# tinyGIANT.net
KiCad netlist of a schematic drawn in EAGLE
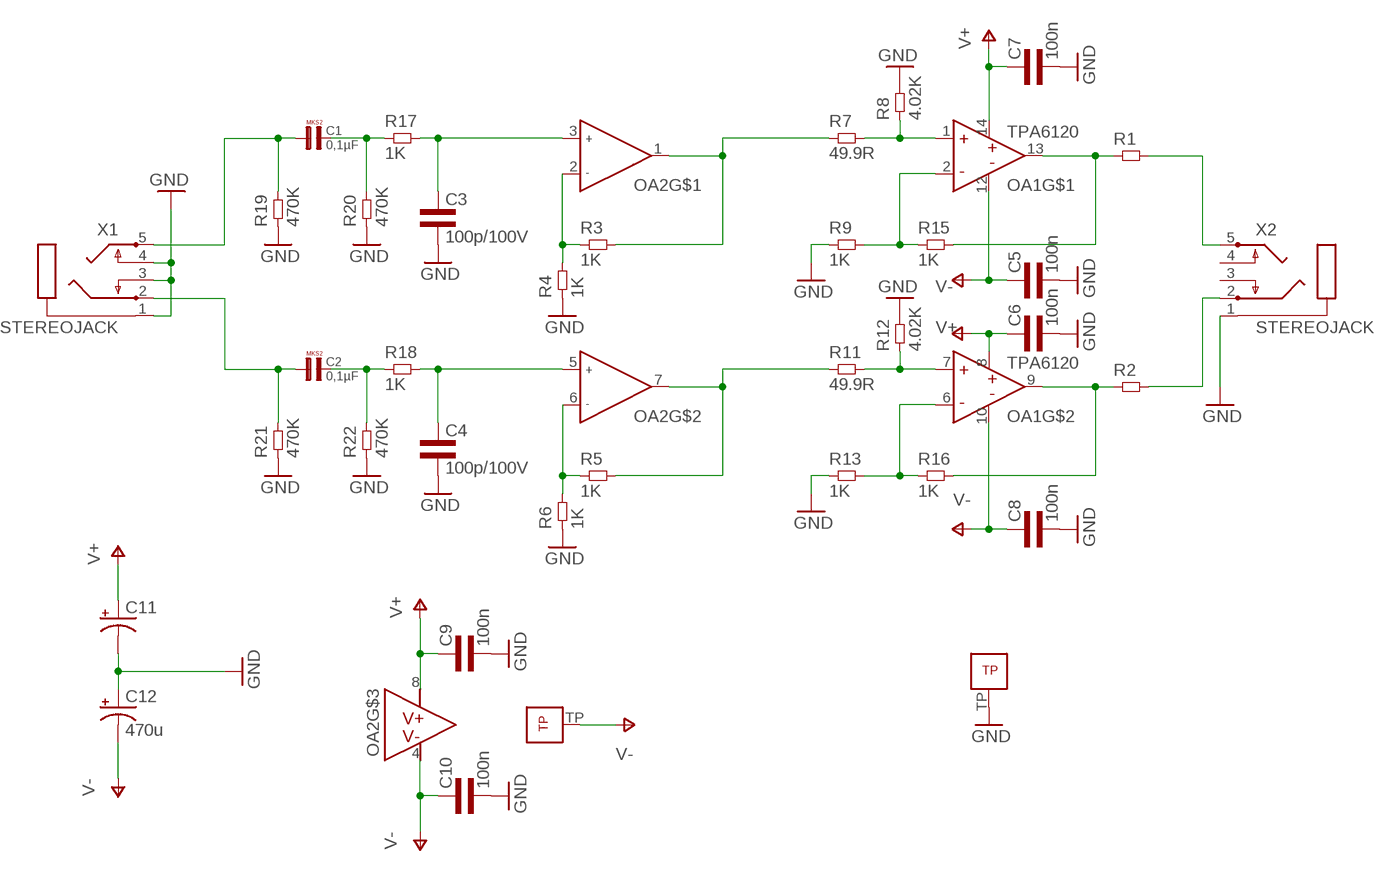
[diagram p0: schematic, sheet 1]

(export (version "E")
  (design (tool "Eeschema 10.0.6"))
  (components
    (comp (ref "C1")
      (value "0,1µF")
      (footprint "eagle-import:R5B2K5")
      (libsource (lib "eagle-import") (part "0,1µF"))
    )
    (comp (ref "C2")
      (value "0,1µF")
      (footprint "eagle-import:R5B2K5")
      (libsource (lib "eagle-import") (part "0,1µF"))
    )
    (comp (ref "C3")
      (value "100p/100V")
      (footprint "eagle-import:0805L3")
      (libsource (lib "eagle-import") (part "CAP0805L3"))
    )
    (comp (ref "C4")
      (value "100p/100V")
      (footprint "eagle-import:0805L3")
      (libsource (lib "eagle-import") (part "CAP0805L3"))
    )
    (comp (ref "C5")
      (value "100n")
      (footprint "eagle-import:0603L3")
      (libsource (lib "eagle-import") (part "CAP0603L3"))
    )
    (comp (ref "C6")
      (value "100n")
      (footprint "eagle-import:0603L3")
      (libsource (lib "eagle-import") (part "CAP0603L3"))
    )
    (comp (ref "C7")
      (value "100n")
      (footprint "eagle-import:0603L3")
      (libsource (lib "eagle-import") (part "CAP0603L3"))
    )
    (comp (ref "C8")
      (value "100n")
      (footprint "eagle-import:0603L3")
      (libsource (lib "eagle-import") (part "CAP0603L3"))
    )
    (comp (ref "C9")
      (value "100n")
      (footprint "eagle-import:0603L3")
      (libsource (lib "eagle-import") (part "CAP0603L3"))
    )
    (comp (ref "C10")
      (value "100n")
      (footprint "eagle-import:0603L3")
      (libsource (lib "eagle-import") (part "CAP0603L3"))
    )
    (comp (ref "C11")
      (value "CPOL-USCT7343")
      (footprint "eagle-import:CT7343")
      (libsource (lib "eagle-import") (part "CPOL-USCT7343"))
    )
    (comp (ref "C12")
      (value "470u")
      (footprint "eagle-import:CT7343")
      (libsource (lib "eagle-import") (part "CPOL-USCT7343"))
    )
    (comp (ref "OA1")
      (value "TPA6120QFN")
      (footprint "eagle-import:S-PVQFN-N14")
      (libsource (lib "eagle-import") (part "TPA6120QFN"))
    )
    (comp (ref "OA2")
      (value "OPA1612")
      (footprint "eagle-import:S-PWSON-N8")
      (libsource (lib "eagle-import") (part "OPA1612"))
    )
    (comp (ref "R1")
      (value "RES1206L3")
      (footprint "eagle-import:1206L3")
      (libsource (lib "eagle-import") (part "RES1206L3"))
    )
    (comp (ref "R2")
      (value "RES1206L3")
      (footprint "eagle-import:1206L3")
      (libsource (lib "eagle-import") (part "RES1206L3"))
    )
    (comp (ref "R3")
      (value "1K")
      (footprint "eagle-import:0603L3")
      (libsource (lib "eagle-import") (part "RES0603L3"))
    )
    (comp (ref "R4")
      (value "1K")
      (footprint "eagle-import:0603L3")
      (libsource (lib "eagle-import") (part "RES0603L3"))
    )
    (comp (ref "R5")
      (value "1K")
      (footprint "eagle-import:0603L3")
      (libsource (lib "eagle-import") (part "RES0603L3"))
    )
    (comp (ref "R6")
      (value "1K")
      (footprint "eagle-import:0603L3")
      (libsource (lib "eagle-import") (part "RES0603L3"))
    )
    (comp (ref "R7")
      (value "49.9R")
      (footprint "eagle-import:0805L3")
      (libsource (lib "eagle-import") (part "RES0805L3"))
    )
    (comp (ref "R8")
      (value "4.02K")
      (footprint "eagle-import:0805L3")
      (libsource (lib "eagle-import") (part "RES0805L3"))
    )
    (comp (ref "R9")
      (value "1K")
      (footprint "eagle-import:0603L3")
      (libsource (lib "eagle-import") (part "RES0603L3"))
    )
    (comp (ref "R11")
      (value "49.9R")
      (footprint "eagle-import:0805L3")
      (libsource (lib "eagle-import") (part "RES0805L3"))
    )
    (comp (ref "R12")
      (value "4.02K")
      (footprint "eagle-import:0805L3")
      (libsource (lib "eagle-import") (part "RES0805L3"))
    )
    (comp (ref "R13")
      (value "1K")
      (footprint "eagle-import:0603L3")
      (libsource (lib "eagle-import") (part "RES0603L3"))
    )
    (comp (ref "R15")
      (value "1K")
      (footprint "eagle-import:0603L3")
      (libsource (lib "eagle-import") (part "RES0603L3"))
    )
    (comp (ref "R16")
      (value "1K")
      (footprint "eagle-import:0603L3")
      (libsource (lib "eagle-import") (part "RES0603L3"))
    )
    (comp (ref "R17")
      (value "1K")
      (footprint "eagle-import:0805L3")
      (libsource (lib "eagle-import") (part "RES0805L3"))
    )
    (comp (ref "R18")
      (value "1K")
      (footprint "eagle-import:0805L3")
      (libsource (lib "eagle-import") (part "RES0805L3"))
    )
    (comp (ref "R19")
      (value "470K")
      (footprint "eagle-import:0805L3")
      (libsource (lib "eagle-import") (part "RES0805L3"))
    )
    (comp (ref "R20")
      (value "470K")
      (footprint "eagle-import:0805L3")
      (libsource (lib "eagle-import") (part "RES0805L3"))
    )
    (comp (ref "R21")
      (value "470K")
      (footprint "eagle-import:0805L3")
      (libsource (lib "eagle-import") (part "RES0805L3"))
    )
    (comp (ref "R22")
      (value "470K")
      (footprint "eagle-import:0805L3")
      (libsource (lib "eagle-import") (part "RES0805L3"))
    )
    (comp (ref "X1")
      (value "STEREOJACK")
      (footprint "eagle-import:STX3100")
      (libsource (lib "eagle-import") (part "STEREOJACK"))
    )
    (comp (ref "X2")
      (value "STEREOJACK")
      (footprint "eagle-import:STX3100")
      (libsource (lib "eagle-import") (part "STEREOJACK"))
    )
  )
  (nets
    (net (code "1") (name "GND") (class "Default")
      (node (ref "C10") (pin "P$2") (pinfunction "2_P$2") (pintype "bidirectional"))
      (node (ref "C11") (pin "-") (pinfunction "-_-") (pintype "passive"))
      (node (ref "C12") (pin "+") (pinfunction "+_+") (pintype "passive"))
      (node (ref "C3") (pin "2") (pinfunction "2_2") (pintype "bidirectional"))
      (node (ref "C4") (pin "2") (pinfunction "2_2") (pintype "bidirectional"))
      (node (ref "C5") (pin "P$2") (pinfunction "2_P$2") (pintype "bidirectional"))
      (node (ref "C6") (pin "P$2") (pinfunction "2_P$2") (pintype "bidirectional"))
      (node (ref "C7") (pin "P$2") (pinfunction "2_P$2") (pintype "bidirectional"))
      (node (ref "C8") (pin "P$2") (pinfunction "2_P$2") (pintype "bidirectional"))
      (node (ref "C9") (pin "P$2") (pinfunction "2_P$2") (pintype "bidirectional"))
      (node (ref "OA1") (pin "TP") (pinfunction "TP_TP") (pintype "bidirectional"))
      (node (ref "R12") (pin "2") (pinfunction "2_2") (pintype "bidirectional"))
      (node (ref "R13") (pin "P$1") (pinfunction "1_P$1") (pintype "bidirectional"))
      (node (ref "R19") (pin "1") (pinfunction "1_1") (pintype "bidirectional"))
      (node (ref "R20") (pin "1") (pinfunction "1_1") (pintype "bidirectional"))
      (node (ref "R21") (pin "1") (pinfunction "1_1") (pintype "bidirectional"))
      (node (ref "R22") (pin "1") (pinfunction "1_1") (pintype "bidirectional"))
      (node (ref "R4") (pin "P$1") (pinfunction "1_P$1") (pintype "bidirectional"))
      (node (ref "R6") (pin "P$1") (pinfunction "1_P$1") (pintype "bidirectional"))
      (node (ref "R8") (pin "2") (pinfunction "2_2") (pintype "bidirectional"))
      (node (ref "R9") (pin "P$1") (pinfunction "1_P$1") (pintype "bidirectional"))
      (node (ref "X1") (pin "1") (pinfunction "1_1") (pintype "passive"))
      (node (ref "X1") (pin "3") (pinfunction "3_3") (pintype "passive"))
      (node (ref "X1") (pin "4") (pinfunction "4_4") (pintype "passive"))
      (node (ref "X2") (pin "1") (pinfunction "1_1") (pintype "passive"))
    )
    (net (code "2") (name "Net-(C1-Pad1)") (class "Default")
      (node (ref "C1") (pin "1") (pinfunction "1_1") (pintype "passive"))
      (node (ref "R19") (pin "2") (pinfunction "2_2") (pintype "bidirectional"))
      (node (ref "X1") (pin "5") (pinfunction "5_5") (pintype "passive"))
    )
    (net (code "3") (name "Net-(C1-Pad2)") (class "Default")
      (node (ref "C1") (pin "2") (pinfunction "2_2") (pintype "passive"))
      (node (ref "R17") (pin "1") (pinfunction "1_1") (pintype "bidirectional"))
      (node (ref "R20") (pin "2") (pinfunction "2_2") (pintype "bidirectional"))
    )
    (net (code "4") (name "Net-(C2-Pad1)") (class "Default")
      (node (ref "C2") (pin "1") (pinfunction "1_1") (pintype "passive"))
      (node (ref "R21") (pin "2") (pinfunction "2_2") (pintype "bidirectional"))
      (node (ref "X1") (pin "2") (pinfunction "2_2") (pintype "passive"))
    )
    (net (code "5") (name "Net-(C2-Pad2)") (class "Default")
      (node (ref "C2") (pin "2") (pinfunction "2_2") (pintype "passive"))
      (node (ref "R18") (pin "1") (pinfunction "1_1") (pintype "bidirectional"))
      (node (ref "R22") (pin "2") (pinfunction "2_2") (pintype "bidirectional"))
    )
    (net (code "6") (name "Net-(OA1A-IN+)") (class "Default")
      (node (ref "OA1") (pin "1") (pinfunction "IN+_1") (pintype "bidirectional"))
      (node (ref "R7") (pin "2") (pinfunction "2_2") (pintype "bidirectional"))
      (node (ref "R8") (pin "1") (pinfunction "1_1") (pintype "bidirectional"))
    )
    (net (code "7") (name "Net-(OA1A-IN-)") (class "Default")
      (node (ref "OA1") (pin "2") (pinfunction "IN-_2") (pintype "bidirectional"))
      (node (ref "R15") (pin "P$1") (pinfunction "1_P$1") (pintype "bidirectional"))
      (node (ref "R9") (pin "P$2") (pinfunction "2_P$2") (pintype "bidirectional"))
    )
    (net (code "8") (name "Net-(OA1A-OUT)") (class "Default")
      (node (ref "OA1") (pin "13") (pinfunction "OUT_13") (pintype "bidirectional"))
      (node (ref "R1") (pin "1") (pinfunction "1_1") (pintype "bidirectional"))
      (node (ref "R15") (pin "P$2") (pinfunction "2_P$2") (pintype "bidirectional"))
    )
    (net (code "9") (name "Net-(OA1B-IN+)") (class "Default")
      (node (ref "OA1") (pin "7") (pinfunction "IN+_7") (pintype "bidirectional"))
      (node (ref "R11") (pin "2") (pinfunction "2_2") (pintype "bidirectional"))
      (node (ref "R12") (pin "1") (pinfunction "1_1") (pintype "bidirectional"))
    )
    (net (code "10") (name "Net-(OA1B-IN-)") (class "Default")
      (node (ref "OA1") (pin "6") (pinfunction "IN-_6") (pintype "bidirectional"))
      (node (ref "R13") (pin "P$2") (pinfunction "2_P$2") (pintype "bidirectional"))
      (node (ref "R16") (pin "P$1") (pinfunction "1_P$1") (pintype "bidirectional"))
    )
    (net (code "11") (name "Net-(OA1B-OUT)") (class "Default")
      (node (ref "OA1") (pin "9") (pinfunction "OUT_9") (pintype "bidirectional"))
      (node (ref "R16") (pin "P$2") (pinfunction "2_P$2") (pintype "bidirectional"))
      (node (ref "R2") (pin "1") (pinfunction "1_1") (pintype "bidirectional"))
    )
    (net (code "12") (name "Net-(OA2A-INA+)") (class "Default")
      (node (ref "C3") (pin "1") (pinfunction "1_1") (pintype "bidirectional"))
      (node (ref "OA2") (pin "3") (pinfunction "INA+_3") (pintype "bidirectional"))
      (node (ref "R17") (pin "2") (pinfunction "2_2") (pintype "bidirectional"))
    )
    (net (code "13") (name "Net-(OA2A-INA-)") (class "Default")
      (node (ref "OA2") (pin "2") (pinfunction "INA-_2") (pintype "bidirectional"))
      (node (ref "R3") (pin "P$1") (pinfunction "1_P$1") (pintype "bidirectional"))
      (node (ref "R4") (pin "P$2") (pinfunction "2_P$2") (pintype "bidirectional"))
    )
    (net (code "14") (name "Net-(OA2A-OUTA)") (class "Default")
      (node (ref "OA2") (pin "1") (pinfunction "OUTA_1") (pintype "bidirectional"))
      (node (ref "R3") (pin "P$2") (pinfunction "2_P$2") (pintype "bidirectional"))
      (node (ref "R7") (pin "1") (pinfunction "1_1") (pintype "bidirectional"))
    )
    (net (code "15") (name "Net-(OA2B-INB+)") (class "Default")
      (node (ref "C4") (pin "1") (pinfunction "1_1") (pintype "bidirectional"))
      (node (ref "OA2") (pin "5") (pinfunction "INB+_5") (pintype "bidirectional"))
      (node (ref "R18") (pin "2") (pinfunction "2_2") (pintype "bidirectional"))
    )
    (net (code "16") (name "Net-(OA2B-INB-)") (class "Default")
      (node (ref "OA2") (pin "6") (pinfunction "INB-_6") (pintype "bidirectional"))
      (node (ref "R5") (pin "P$1") (pinfunction "1_P$1") (pintype "bidirectional"))
      (node (ref "R6") (pin "P$2") (pinfunction "2_P$2") (pintype "bidirectional"))
    )
    (net (code "17") (name "Net-(OA2B-OUTB)") (class "Default")
      (node (ref "OA2") (pin "7") (pinfunction "OUTB_7") (pintype "bidirectional"))
      (node (ref "R11") (pin "1") (pinfunction "1_1") (pintype "bidirectional"))
      (node (ref "R5") (pin "P$2") (pinfunction "2_P$2") (pintype "bidirectional"))
    )
    (net (code "18") (name "Net-(R1-Pad2)") (class "Default")
      (node (ref "R1") (pin "2") (pinfunction "2_2") (pintype "bidirectional"))
      (node (ref "X2") (pin "5") (pinfunction "5_5") (pintype "passive"))
    )
    (net (code "19") (name "Net-(R2-Pad2)") (class "Default")
      (node (ref "R2") (pin "2") (pinfunction "2_2") (pintype "bidirectional"))
      (node (ref "X2") (pin "2") (pinfunction "2_2") (pintype "passive"))
    )
    (net (code "20") (name "V+") (class "Default")
      (node (ref "C11") (pin "+") (pinfunction "+_+") (pintype "passive"))
      (node (ref "C6") (pin "P$1") (pinfunction "1_P$1") (pintype "bidirectional"))
      (node (ref "C7") (pin "P$1") (pinfunction "1_P$1") (pintype "bidirectional"))
      (node (ref "C9") (pin "P$1") (pinfunction "1_P$1") (pintype "bidirectional"))
      (node (ref "OA1") (pin "14") (pinfunction "V+_14") (pintype "bidirectional"))
      (node (ref "OA1") (pin "8") (pinfunction "V+_8") (pintype "bidirectional"))
      (node (ref "OA2") (pin "8") (pinfunction "V+_8") (pintype "power_in"))
    )
    (net (code "21") (name "V-") (class "Default")
      (node (ref "C10") (pin "P$1") (pinfunction "1_P$1") (pintype "bidirectional"))
      (node (ref "C12") (pin "-") (pinfunction "-_-") (pintype "passive"))
      (node (ref "C5") (pin "P$1") (pinfunction "1_P$1") (pintype "bidirectional"))
      (node (ref "C8") (pin "P$1") (pinfunction "1_P$1") (pintype "bidirectional"))
      (node (ref "OA1") (pin "10") (pinfunction "V-_10") (pintype "bidirectional"))
      (node (ref "OA1") (pin "12") (pinfunction "V-_12") (pintype "bidirectional"))
      (node (ref "OA2") (pin "4") (pinfunction "V-_4") (pintype "power_in"))
      (node (ref "OA2") (pin "TP") (pinfunction "TP_TP") (pintype "bidirectional"))
    )
    (net (code "22") (name "unconnected-(X2-Pad3)") (class "Default")
      (node (ref "X2") (pin "3") (pinfunction "3_3") (pintype "passive"))
    )
    (net (code "23") (name "unconnected-(X2-Pad4)") (class "Default")
      (node (ref "X2") (pin "4") (pinfunction "4_4") (pintype "passive"))
    )
  )
)
